# OpIoT_v_1_2.net
KiCad netlist of a schematic drawn in EAGLE
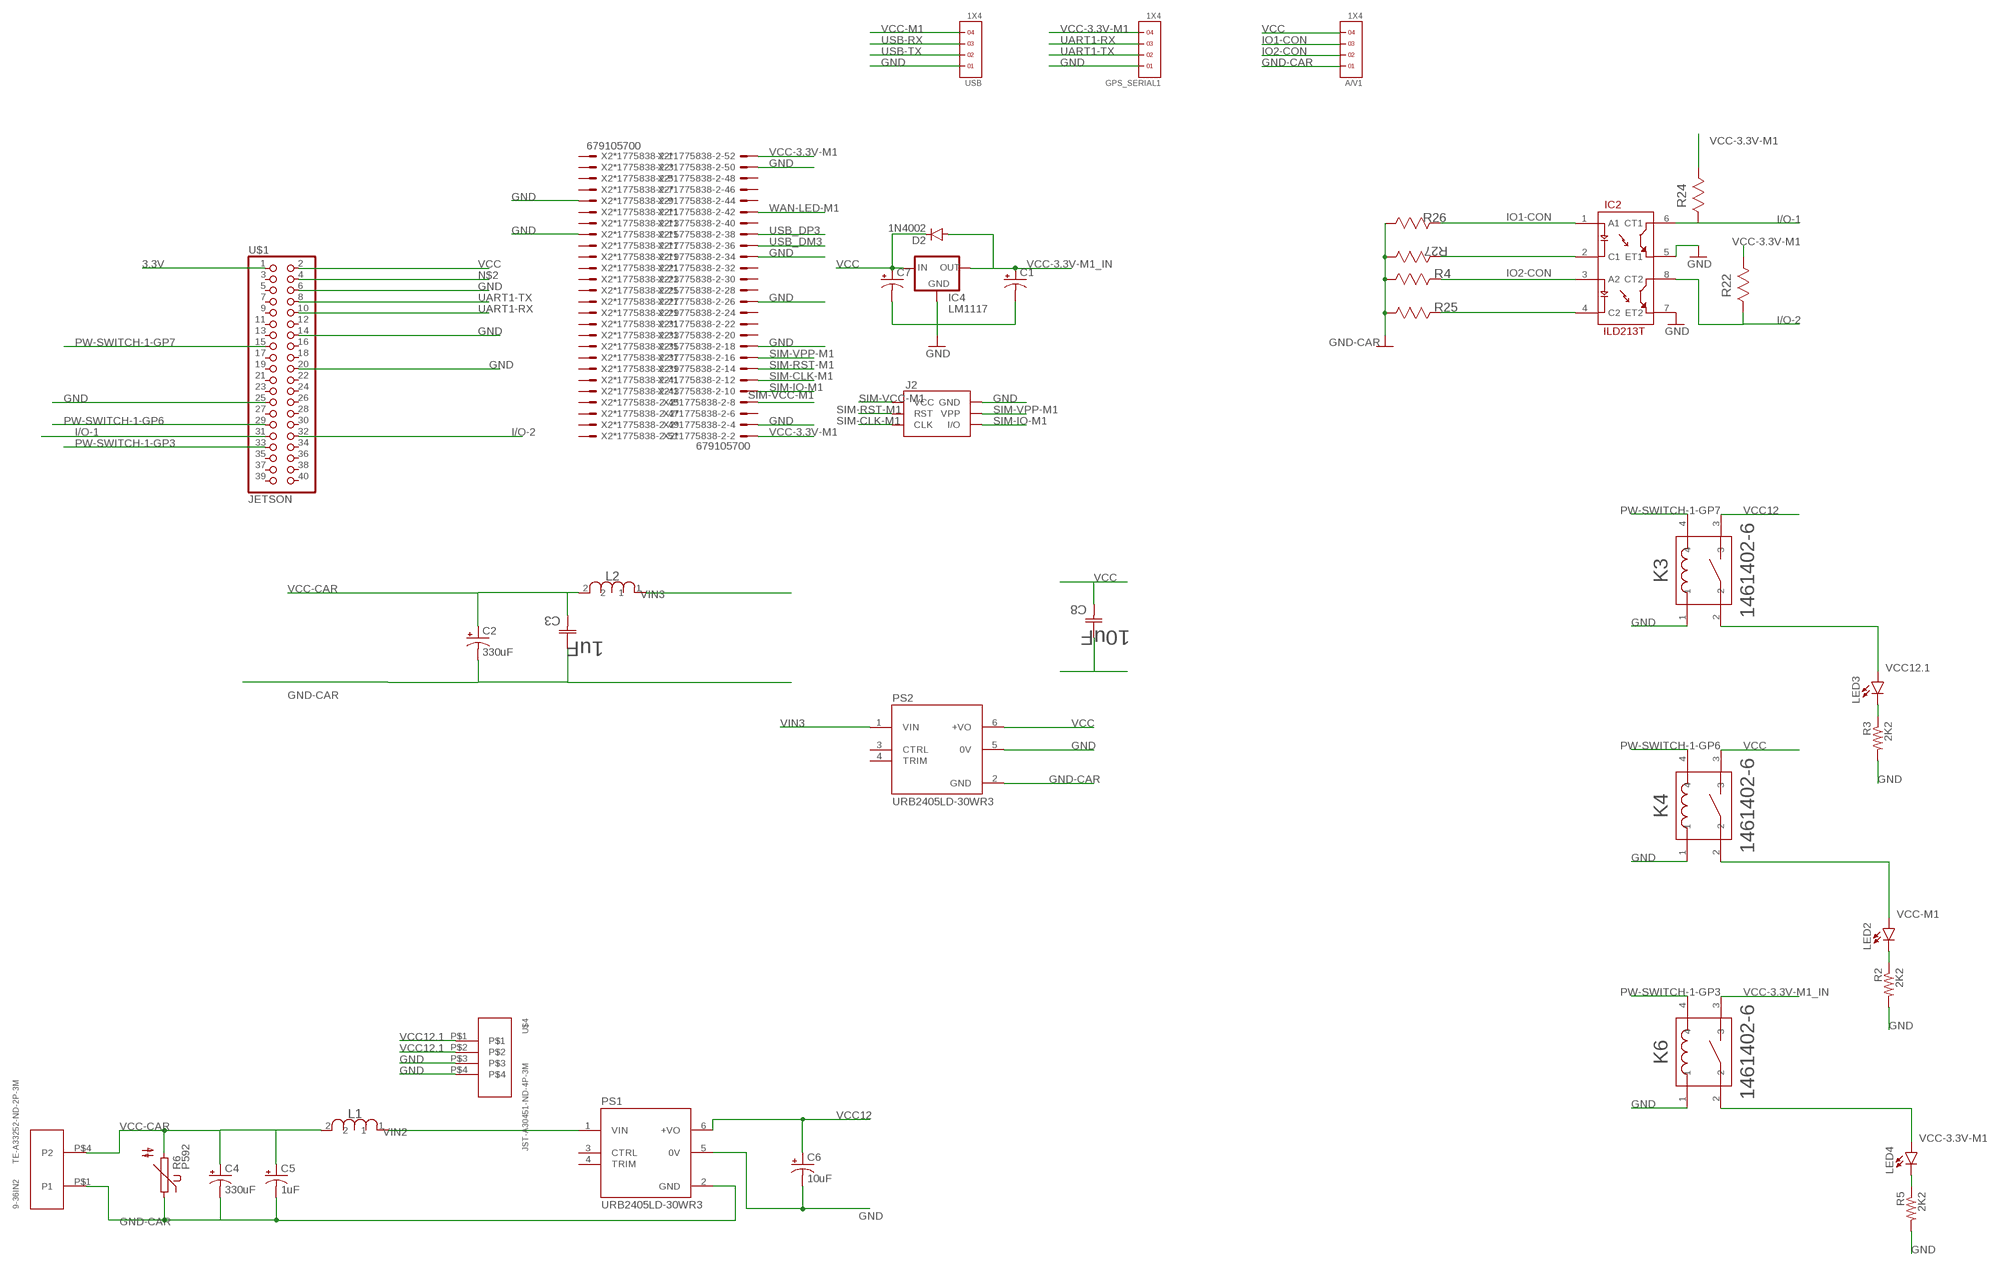
[diagram p0: schematic, sheet 1]

(export (version "E")
  (design (tool "Eeschema 10.0.6"))
  (components
    (comp (ref "9-36IN2")
      (value "TE-A33252-ND-2P-3M")
      (footprint "eagle-import:TE-A33252-ND-2P-3M")
      (libsource (lib "eagle-import") (part "TE-A33252-ND-2P-3M"))
    )
    (comp (ref "A/V1")
      (value "1X4")
      (footprint "eagle-import:1X4")
      (libsource (lib "eagle-import") (part "1X4"))
    )
    (comp (ref "C1")
      (value "CAP_POL1206-KIT")
      (footprint "eagle-import:EIA3216-KIT")
      (libsource (lib "eagle-import") (part "CAP_POL1206-KIT"))
    )
    (comp (ref "C2")
      (value "330uF")
      (footprint "eagle-import:UD-10X10_NICHICON")
      (libsource (lib "eagle-import") (part "CPOL-USUD-10X10"))
    )
    (comp (ref "C3")
      (value "1uF")
      (footprint "eagle-import:CAPC3216X110N")
      (fields (field (name "MPN") "C1206C105K5RACTU") (field (name "TOLERANCE") "±10%"))
      (libsource (lib "eagle-import") (part "C1206C105K5RACTU"))
    )
    (comp (ref "C4")
      (value "330uF")
      (footprint "eagle-import:UD-10X10_NICHICON")
      (libsource (lib "eagle-import") (part "CPOL-USUD-10X10"))
    )
    (comp (ref "C5")
      (value "1uF")
      (footprint "eagle-import:EIA3216-KIT")
      (libsource (lib "eagle-import") (part "CAP_POL1206-KIT"))
    )
    (comp (ref "C6")
      (value "10uF")
      (footprint "eagle-import:EIA3216-KIT")
      (libsource (lib "eagle-import") (part "CAP_POL1206-KIT"))
    )
    (comp (ref "C7")
      (value "CAP_POL1206-KIT")
      (footprint "eagle-import:EIA3216-KIT")
      (libsource (lib "eagle-import") (part "CAP_POL1206-KIT"))
    )
    (comp (ref "C8")
      (value "10uF")
      (footprint "eagle-import:CAPC3216X110N")
      (fields (field (name "MPN") "C1206C105K5RACTU") (field (name "TOLERANCE") "±10%"))
      (libsource (lib "eagle-import") (part "C1206C105K5RACTU"))
    )
    (comp (ref "D2")
      (value "1N4002")
      (footprint "eagle-import:SMA-DIODE-KIT")
      (libsource (lib "eagle-import") (part "DIODESMA-KIT"))
    )
    (comp (ref "GPS_SERIAL1")
      (value "1X4")
      (footprint "eagle-import:1X4")
      (libsource (lib "eagle-import") (part "1X4"))
    )
    (comp (ref "IC2")
      (value "ILD213T")
      (footprint "eagle-import:SO08")
      (libsource (lib "eagle-import") (part "ILD213T"))
    )
    (comp (ref "IC4")
      (value "LM1117")
      (footprint "eagle-import:SOT223")
      (fields (field (name "MF") "Texas Instruments") (field (name "MP") "LM1117MP-3.3/NOPB"))
      (libsource (lib "eagle-import") (part "LM1117"))
    )
    (comp (ref "J2")
      (value "SIMHOLDERSIM")
      (footprint "eagle-import:SIMHOLDER")
      (libsource (lib "eagle-import") (part "SIMHOLDERSIM"))
    )
    (comp (ref "K3")
      (value "1461402-6")
      (footprint "eagle-import:RELAY_1461402-6")
      (fields (field (name "MF") "TE Connectivity") (field (name "MP") "OJE-SH-112HM,000"))
      (libsource (lib "eagle-import") (part "1461402-6"))
    )
    (comp (ref "K4")
      (value "1461402-6")
      (footprint "eagle-import:RELAY_1461402-6")
      (fields (field (name "MF") "TE Connectivity") (field (name "MP") "OJE-SH-112HM,000"))
      (libsource (lib "eagle-import") (part "1461402-6"))
    )
    (comp (ref "K6")
      (value "1461402-6")
      (footprint "eagle-import:RELAY_1461402-6")
      (fields (field (name "MF") "TE Connectivity") (field (name "MP") "OJE-SH-112HM,000"))
      (libsource (lib "eagle-import") (part "1461402-6"))
    )
    (comp (ref "L1")
      (value "4.7uH")
      (footprint "eagle-import:INDC3225X22N")
      (fields (field (name "MPN") "PM1210-1R0J-RC") (field (name "TOLERANCE") "±5 %"))
      (libsource (lib "eagle-import") (part "PM1210-1R0J-RC"))
    )
    (comp (ref "L2")
      (value "4.7uH")
      (footprint "eagle-import:INDC3225X22N")
      (fields (field (name "MPN") "PM1210-1R0J-RC") (field (name "TOLERANCE") "±5 %"))
      (libsource (lib "eagle-import") (part "PM1210-1R0J-RC"))
    )
    (comp (ref "LED2")
      (value "LEDCHIPLED_1206")
      (footprint "eagle-import:CHIPLED_1206")
      (libsource (lib "eagle-import") (part "LEDCHIPLED_1206"))
    )
    (comp (ref "LED3")
      (value "LEDCHIPLED_1206")
      (footprint "eagle-import:CHIPLED_1206")
      (libsource (lib "eagle-import") (part "LEDCHIPLED_1206"))
    )
    (comp (ref "LED4")
      (value "LEDCHIPLED_1206")
      (footprint "eagle-import:CHIPLED_1206")
      (libsource (lib "eagle-import") (part "LEDCHIPLED_1206"))
    )
    (comp (ref "PS1")
      (value "URB2405LD-30WR3")
      (footprint "eagle-import:CONV_URB2405LD-30WR3")
      (fields (field (name "MF") "MORNSUN"))
      (libsource (lib "eagle-import") (part "URB2405LD-30WR3"))
    )
    (comp (ref "PS2")
      (value "URB2405LD-30WR3")
      (footprint "eagle-import:CONV_URB2405LD-30WR3")
      (fields (field (name "MF") "MORNSUN"))
      (libsource (lib "eagle-import") (part "URB2405LD-30WR3"))
    )
    (comp (ref "R2")
      (value "2K2")
      (footprint "eagle-import:M1206")
      (libsource (lib "eagle-import") (part "R-US_M1206"))
    )
    (comp (ref "R3")
      (value "2K2")
      (footprint "eagle-import:M1206")
      (libsource (lib "eagle-import") (part "R-US_M1206"))
    )
    (comp (ref "R4")
      (value "4K7")
      (footprint "eagle-import:RESC3216X71N")
      (fields (field (name "MPN") "ERJ-8ENF1501V") (field (name "TOLERANCE") "±1 %"))
      (libsource (lib "eagle-import") (part "ERJ-8ENF1501V"))
    )
    (comp (ref "R5")
      (value "2K2")
      (footprint "eagle-import:M1206")
      (libsource (lib "eagle-import") (part "R-US_M1206"))
    )
    (comp (ref "R6")
      (value "P592")
      (footprint "eagle-import:P592")
      (libsource (lib "eagle-import") (part "P592"))
    )
    (comp (ref "R22")
      (value "300K")
      (footprint "eagle-import:RESC3216X71N")
      (fields (field (name "MPN") "ERJ-8ENF1501V") (field (name "TOLERANCE") "±1 %"))
      (libsource (lib "eagle-import") (part "ERJ-8ENF1501V"))
    )
    (comp (ref "R24")
      (value "300K")
      (footprint "eagle-import:RESC3216X71N")
      (fields (field (name "MPN") "ERJ-8ENF1501V") (field (name "TOLERANCE") "±1 %"))
      (libsource (lib "eagle-import") (part "ERJ-8ENF1501V"))
    )
    (comp (ref "R25")
      (value "2.2K")
      (footprint "eagle-import:RESC3216X71N")
      (fields (field (name "MPN") "ERJ-8ENF1501V") (field (name "TOLERANCE") "±1 %"))
      (libsource (lib "eagle-import") (part "ERJ-8ENF1501V"))
    )
    (comp (ref "R26")
      (value "4K7")
      (footprint "eagle-import:RESC3216X71N")
      (fields (field (name "MPN") "ERJ-8ENF1501V") (field (name "TOLERANCE") "±1 %"))
      (libsource (lib "eagle-import") (part "ERJ-8ENF1501V"))
    )
    (comp (ref "R27")
      (value "2.2K")
      (footprint "eagle-import:RESC3216X71N")
      (fields (field (name "MPN") "ERJ-8ENF1501V") (field (name "TOLERANCE") "±1 %"))
      (libsource (lib "eagle-import") (part "ERJ-8ENF1501V"))
    )
    (comp (ref "U$1")
      (value "JETSON")
      (footprint "eagle-import:2X20")
      (libsource (lib "eagle-import") (part "JETSON"))
    )
    (comp (ref "U$4")
      (value "JST-A30451-ND-4P-3M")
      (footprint "eagle-import:TE-A30451-4P-TH-3M")
      (libsource (lib "eagle-import") (part "JST-A30451-ND-4P-3M"))
    )
    (comp (ref "USB")
      (value "1X4")
      (footprint "eagle-import:1X4")
      (libsource (lib "eagle-import") (part "1X4"))
    )
    (comp (ref "X2*1775838-2")
      (value "679105700")
      (footprint "eagle-import:679105700")
      (fields (field (name "MF") "MOLEX") (field (name "MPN") "67910-5700"))
      (libsource (lib "eagle-import") (part "679105700"))
    )
  )
  (nets
    (net (code "1") (name "/3.3V") (class "Default")
      (node (ref "U$1") (pin "1") (pinfunction "1_1") (pintype "passive"))
    )
    (net (code "2") (name "/IO1-CON") (class "Default")
      (node (ref "A/V1") (pin "3") (pinfunction "3_3") (pintype "bidirectional"))
      (node (ref "IC2") (pin "1") (pinfunction "A1_1") (pintype "bidirectional"))
      (node (ref "R26") (pin "1") (pinfunction "R1_1") (pintype "passive"))
    )
    (net (code "3") (name "/IO2-CON") (class "Default")
      (node (ref "A/V1") (pin "2") (pinfunction "2_2") (pintype "bidirectional"))
      (node (ref "IC2") (pin "3") (pinfunction "A2_3") (pintype "bidirectional"))
      (node (ref "R4") (pin "1") (pinfunction "R1_1") (pintype "passive"))
    )
    (net (code "4") (name "/I{slash}O-1") (class "Default")
      (node (ref "IC2") (pin "6") (pinfunction "CT1_6") (pintype "bidirectional"))
      (node (ref "R24") (pin "2") (pinfunction "R2_2") (pintype "passive"))
      (node (ref "U$1") (pin "31") (pinfunction "31_31") (pintype "passive"))
    )
    (net (code "5") (name "/I{slash}O-2") (class "Default")
      (node (ref "IC2") (pin "8") (pinfunction "CT2_8") (pintype "bidirectional"))
      (node (ref "R22") (pin "2") (pinfunction "R2_2") (pintype "passive"))
      (node (ref "U$1") (pin "32") (pinfunction "32_32") (pintype "passive"))
    )
    (net (code "6") (name "/N$2") (class "Default")
      (node (ref "U$1") (pin "4") (pinfunction "4_4") (pintype "passive"))
    )
    (net (code "7") (name "/PW-SWITCH-1-GP3") (class "Default")
      (node (ref "K6") (pin "4") (pinfunction "4_4") (pintype "passive"))
      (node (ref "U$1") (pin "33") (pinfunction "33_33") (pintype "passive"))
    )
    (net (code "8") (name "/PW-SWITCH-1-GP6") (class "Default")
      (node (ref "K4") (pin "4") (pinfunction "4_4") (pintype "passive"))
      (node (ref "U$1") (pin "29") (pinfunction "29_29") (pintype "passive"))
    )
    (net (code "9") (name "/PW-SWITCH-1-GP7") (class "Default")
      (node (ref "K3") (pin "4") (pinfunction "4_4") (pintype "passive"))
      (node (ref "U$1") (pin "15") (pinfunction "15_15") (pintype "passive"))
    )
    (net (code "10") (name "/SIM-CLK-M1") (class "Default")
      (node (ref "J2") (pin "C3") (pinfunction "CLK_C3") (pintype "input"))
      (node (ref "X2*1775838-2") (pin "12") (pinfunction "S_12") (pintype "passive"))
    )
    (net (code "11") (name "/SIM-IO-M1") (class "Default")
      (node (ref "J2") (pin "C7") (pinfunction "I/O_C7") (pintype "bidirectional"))
      (node (ref "X2*1775838-2") (pin "10") (pinfunction "S_10") (pintype "passive"))
    )
    (net (code "12") (name "/SIM-RST-M1") (class "Default")
      (node (ref "J2") (pin "C2") (pinfunction "RST_C2") (pintype "input"))
      (node (ref "X2*1775838-2") (pin "14") (pinfunction "S_14") (pintype "passive"))
    )
    (net (code "13") (name "/SIM-VCC-M1") (class "Default")
      (node (ref "J2") (pin "C1") (pinfunction "VCC_C1") (pintype "power_in"))
      (node (ref "X2*1775838-2") (pin "8") (pinfunction "S_8") (pintype "passive"))
    )
    (net (code "14") (name "/SIM-VPP-M1") (class "Default")
      (node (ref "J2") (pin "C6") (pinfunction "VPP_C6") (pintype "input"))
      (node (ref "X2*1775838-2") (pin "16") (pinfunction "S_16") (pintype "passive"))
    )
    (net (code "15") (name "/UART1-RX") (class "Default")
      (node (ref "GPS_SERIAL1") (pin "3") (pinfunction "3_3") (pintype "bidirectional"))
      (node (ref "U$1") (pin "10") (pinfunction "10_10") (pintype "passive"))
    )
    (net (code "16") (name "/UART1-TX") (class "Default")
      (node (ref "GPS_SERIAL1") (pin "2") (pinfunction "2_2") (pintype "bidirectional"))
      (node (ref "U$1") (pin "8") (pinfunction "8_8") (pintype "passive"))
    )
    (net (code "17") (name "/USB-RX") (class "Default")
      (node (ref "USB") (pin "3") (pinfunction "3_3") (pintype "bidirectional"))
    )
    (net (code "18") (name "/USB-TX") (class "Default")
      (node (ref "USB") (pin "2") (pinfunction "2_2") (pintype "bidirectional"))
    )
    (net (code "19") (name "/USB_DM3") (class "Default")
      (node (ref "X2*1775838-2") (pin "36") (pinfunction "S_36") (pintype "passive"))
    )
    (net (code "20") (name "/USB_DP3") (class "Default")
      (node (ref "X2*1775838-2") (pin "38") (pinfunction "S_38") (pintype "passive"))
    )
    (net (code "21") (name "/VCC") (class "Default")
      (node (ref "A/V1") (pin "4") (pinfunction "4_4") (pintype "bidirectional"))
      (node (ref "C7") (pin "A") (pinfunction "+_A") (pintype "passive"))
      (node (ref "C8") (pin "2") (pinfunction "C2_2") (pintype "passive"))
      (node (ref "D2") (pin "C") (pinfunction "C_C") (pintype "passive"))
      (node (ref "IC4") (pin "3") (pinfunction "IN_3") (pintype "input"))
      (node (ref "K4") (pin "3") (pinfunction "3_3") (pintype "passive"))
      (node (ref "PS2") (pin "6") (pinfunction "+VO_6") (pintype "output"))
      (node (ref "U$1") (pin "2") (pinfunction "2_2") (pintype "passive"))
    )
    (net (code "22") (name "/VCC-3.3V-M1") (class "Default")
      (node (ref "GPS_SERIAL1") (pin "4") (pinfunction "4_4") (pintype "bidirectional"))
      (node (ref "K6") (pin "2") (pinfunction "2_2") (pintype "passive"))
      (node (ref "LED4") (pin "A") (pinfunction "A_A") (pintype "passive"))
      (node (ref "R22") (pin "1") (pinfunction "R1_1") (pintype "passive"))
      (node (ref "R24") (pin "1") (pinfunction "R1_1") (pintype "passive"))
      (node (ref "X2*1775838-2") (pin "2") (pinfunction "S_2") (pintype "passive"))
      (node (ref "X2*1775838-2") (pin "52") (pinfunction "S_52") (pintype "passive"))
    )
    (net (code "23") (name "/VCC-3.3V-M1_IN") (class "Default")
      (node (ref "C1") (pin "A") (pinfunction "+_A") (pintype "passive"))
      (node (ref "D2") (pin "A") (pinfunction "A_A") (pintype "passive"))
      (node (ref "IC4") (pin "2") (pinfunction "OUT_2") (pintype "passive"))
      (node (ref "K6") (pin "3") (pinfunction "3_3") (pintype "passive"))
    )
    (net (code "24") (name "/VCC-CAR") (class "Default")
      (node (ref "9-36IN2") (pin "P$4") (pinfunction "P2_P$4") (pintype "bidirectional"))
      (node (ref "C2") (pin "+") (pinfunction "+_+") (pintype "passive"))
      (node (ref "C3") (pin "2") (pinfunction "C2_2") (pintype "passive"))
      (node (ref "C4") (pin "+") (pinfunction "+_+") (pintype "passive"))
      (node (ref "C5") (pin "A") (pinfunction "+_A") (pintype "passive"))
      (node (ref "L1") (pin "2") (pinfunction "2_2") (pintype "passive"))
      (node (ref "L2") (pin "2") (pinfunction "2_2") (pintype "passive"))
      (node (ref "R6") (pin "2") (pinfunction "2_2") (pintype "passive"))
    )
    (net (code "25") (name "/VCC-M1") (class "Default")
      (node (ref "K4") (pin "2") (pinfunction "2_2") (pintype "passive"))
      (node (ref "LED2") (pin "A") (pinfunction "A_A") (pintype "passive"))
      (node (ref "USB") (pin "4") (pinfunction "4_4") (pintype "bidirectional"))
    )
    (net (code "26") (name "/VCC12") (class "Default")
      (node (ref "C6") (pin "A") (pinfunction "+_A") (pintype "passive"))
      (node (ref "K3") (pin "3") (pinfunction "3_3") (pintype "passive"))
      (node (ref "PS1") (pin "6") (pinfunction "+VO_6") (pintype "output"))
    )
    (net (code "27") (name "/VCC12.1") (class "Default")
      (node (ref "K3") (pin "2") (pinfunction "2_2") (pintype "passive"))
      (node (ref "LED3") (pin "A") (pinfunction "A_A") (pintype "passive"))
      (node (ref "U$4") (pin "P$1") (pinfunction "P$1_P$1") (pintype "bidirectional"))
      (node (ref "U$4") (pin "P$2") (pinfunction "P$2_P$2") (pintype "bidirectional"))
    )
    (net (code "28") (name "/VIN2") (class "Default")
      (node (ref "L1") (pin "1") (pinfunction "1_1") (pintype "passive"))
      (node (ref "PS1") (pin "1") (pinfunction "VIN_1") (pintype "input"))
    )
    (net (code "29") (name "/VIN3") (class "Default")
      (node (ref "L2") (pin "1") (pinfunction "1_1") (pintype "passive"))
      (node (ref "PS2") (pin "1") (pinfunction "VIN_1") (pintype "input"))
    )
    (net (code "30") (name "/WAN-LED-M1") (class "Default")
      (node (ref "X2*1775838-2") (pin "42") (pinfunction "S_42") (pintype "passive"))
    )
    (net (code "31") (name "GND") (class "Default")
      (node (ref "C1") (pin "C") (pinfunction "-_C") (pintype "passive"))
      (node (ref "C6") (pin "C") (pinfunction "-_C") (pintype "passive"))
      (node (ref "C7") (pin "C") (pinfunction "-_C") (pintype "passive"))
      (node (ref "C8") (pin "1") (pinfunction "C1_1") (pintype "passive"))
      (node (ref "GPS_SERIAL1") (pin "1") (pinfunction "1_1") (pintype "bidirectional"))
      (node (ref "IC2") (pin "5") (pinfunction "ET1_5") (pintype "bidirectional"))
      (node (ref "IC2") (pin "7") (pinfunction "ET2_7") (pintype "bidirectional"))
      (node (ref "IC4") (pin "1") (pinfunction "GND_1") (pintype "input"))
      (node (ref "J2") (pin "C5") (pinfunction "GND_C5") (pintype "power_in"))
      (node (ref "K3") (pin "1") (pinfunction "1_1") (pintype "passive"))
      (node (ref "K4") (pin "1") (pinfunction "1_1") (pintype "passive"))
      (node (ref "K6") (pin "1") (pinfunction "1_1") (pintype "passive"))
      (node (ref "PS1") (pin "5") (pinfunction "0V_5") (pintype "output"))
      (node (ref "PS2") (pin "5") (pinfunction "0V_5") (pintype "output"))
      (node (ref "R2") (pin "2") (pinfunction "2_2") (pintype "passive"))
      (node (ref "R3") (pin "2") (pinfunction "2_2") (pintype "passive"))
      (node (ref "R5") (pin "2") (pinfunction "2_2") (pintype "passive"))
      (node (ref "U$1") (pin "14") (pinfunction "14_14") (pintype "passive"))
      (node (ref "U$1") (pin "20") (pinfunction "20_20") (pintype "passive"))
      (node (ref "U$1") (pin "25") (pinfunction "25_25") (pintype "passive"))
      (node (ref "U$1") (pin "6") (pinfunction "6_6") (pintype "passive"))
      (node (ref "U$4") (pin "P$3") (pinfunction "P$3_P$3") (pintype "bidirectional"))
      (node (ref "U$4") (pin "P$4") (pinfunction "P$4_P$4") (pintype "bidirectional"))
      (node (ref "USB") (pin "1") (pinfunction "1_1") (pintype "bidirectional"))
      (node (ref "X2*1775838-2") (pin "15") (pinfunction "S_15") (pintype "passive"))
      (node (ref "X2*1775838-2") (pin "18") (pinfunction "S_18") (pintype "passive"))
      (node (ref "X2*1775838-2") (pin "26") (pinfunction "S_26") (pintype "passive"))
      (node (ref "X2*1775838-2") (pin "34") (pinfunction "S_34") (pintype "passive"))
      (node (ref "X2*1775838-2") (pin "4") (pinfunction "S_4") (pintype "passive"))
      (node (ref "X2*1775838-2") (pin "50") (pinfunction "S_50") (pintype "passive"))
      (node (ref "X2*1775838-2") (pin "9") (pinfunction "S_9") (pintype "passive"))
    )
    (net (code "32") (name "GND-CAR") (class "Default")
      (node (ref "9-36IN2") (pin "P$1") (pinfunction "P1_P$1") (pintype "bidirectional"))
      (node (ref "A/V1") (pin "1") (pinfunction "1_1") (pintype "bidirectional"))
      (node (ref "C2") (pin "-") (pinfunction "-_-") (pintype "passive"))
      (node (ref "C3") (pin "1") (pinfunction "C1_1") (pintype "passive"))
      (node (ref "C4") (pin "-") (pinfunction "-_-") (pintype "passive"))
      (node (ref "C5") (pin "C") (pinfunction "-_C") (pintype "passive"))
      (node (ref "PS1") (pin "2") (pinfunction "GND_2") (pintype "power_in"))
      (node (ref "PS2") (pin "2") (pinfunction "GND_2") (pintype "power_in"))
      (node (ref "R25") (pin "1") (pinfunction "R1_1") (pintype "passive"))
      (node (ref "R26") (pin "2") (pinfunction "R2_2") (pintype "passive"))
      (node (ref "R27") (pin "1") (pinfunction "R1_1") (pintype "passive"))
      (node (ref "R4") (pin "2") (pinfunction "R2_2") (pintype "passive"))
      (node (ref "R6") (pin "1") (pinfunction "1_1") (pintype "passive"))
    )
    (net (code "33") (name "Net-(IC2-C1)") (class "Default")
      (node (ref "IC2") (pin "2") (pinfunction "C1_2") (pintype "bidirectional"))
      (node (ref "R27") (pin "2") (pinfunction "R2_2") (pintype "passive"))
    )
    (net (code "34") (name "Net-(IC2-C2)") (class "Default")
      (node (ref "IC2") (pin "4") (pinfunction "C2_4") (pintype "bidirectional"))
      (node (ref "R25") (pin "2") (pinfunction "R2_2") (pintype "passive"))
    )
    (net (code "35") (name "Net-(LED2-PadC)") (class "Default")
      (node (ref "LED2") (pin "C") (pinfunction "C_C") (pintype "passive"))
      (node (ref "R2") (pin "1") (pinfunction "1_1") (pintype "passive"))
    )
    (net (code "36") (name "Net-(LED3-PadC)") (class "Default")
      (node (ref "LED3") (pin "C") (pinfunction "C_C") (pintype "passive"))
      (node (ref "R3") (pin "1") (pinfunction "1_1") (pintype "passive"))
    )
    (net (code "37") (name "Net-(LED4-PadC)") (class "Default")
      (node (ref "LED4") (pin "C") (pinfunction "C_C") (pintype "passive"))
      (node (ref "R5") (pin "1") (pinfunction "1_1") (pintype "passive"))
    )
    (net (code "38") (name "unconnected-(PS1-CTRL-Pad3)") (class "Default")
      (node (ref "PS1") (pin "3") (pinfunction "CTRL_3") (pintype "input"))
    )
    (net (code "39") (name "unconnected-(PS1-TRIM-Pad4)") (class "Default")
      (node (ref "PS1") (pin "4") (pinfunction "TRIM_4") (pintype "input"))
    )
    (net (code "40") (name "unconnected-(PS2-CTRL-Pad3)") (class "Default")
      (node (ref "PS2") (pin "3") (pinfunction "CTRL_3") (pintype "input"))
    )
    (net (code "41") (name "unconnected-(PS2-TRIM-Pad4)") (class "Default")
      (node (ref "PS2") (pin "4") (pinfunction "TRIM_4") (pintype "input"))
    )
    (net (code "42") (name "unconnected-(U$1-Pad3)") (class "Default")
      (node (ref "U$1") (pin "3") (pinfunction "3_3") (pintype "passive"))
    )
    (net (code "43") (name "unconnected-(U$1-Pad5)") (class "Default")
      (node (ref "U$1") (pin "5") (pinfunction "5_5") (pintype "passive"))
    )
    (net (code "44") (name "unconnected-(U$1-Pad7)") (class "Default")
      (node (ref "U$1") (pin "7") (pinfunction "7_7") (pintype "passive"))
    )
    (net (code "45") (name "unconnected-(U$1-Pad9)") (class "Default")
      (node (ref "U$1") (pin "9") (pinfunction "9_9") (pintype "passive"))
    )
    (net (code "46") (name "unconnected-(U$1-Pad11)") (class "Default")
      (node (ref "U$1") (pin "11") (pinfunction "11_11") (pintype "passive"))
    )
    (net (code "47") (name "unconnected-(U$1-Pad12)") (class "Default")
      (node (ref "U$1") (pin "12") (pinfunction "12_12") (pintype "passive"))
    )
    (net (code "48") (name "unconnected-(U$1-Pad13)") (class "Default")
      (node (ref "U$1") (pin "13") (pinfunction "13_13") (pintype "passive"))
    )
    (net (code "49") (name "unconnected-(U$1-Pad16)") (class "Default")
      (node (ref "U$1") (pin "16") (pinfunction "16_16") (pintype "passive"))
    )
    (net (code "50") (name "unconnected-(U$1-Pad17)") (class "Default")
      (node (ref "U$1") (pin "17") (pinfunction "17_17") (pintype "passive"))
    )
    (net (code "51") (name "unconnected-(U$1-Pad18)") (class "Default")
      (node (ref "U$1") (pin "18") (pinfunction "18_18") (pintype "passive"))
    )
    (net (code "52") (name "unconnected-(U$1-Pad19)") (class "Default")
      (node (ref "U$1") (pin "19") (pinfunction "19_19") (pintype "passive"))
    )
    (net (code "53") (name "unconnected-(U$1-Pad21)") (class "Default")
      (node (ref "U$1") (pin "21") (pinfunction "21_21") (pintype "passive"))
    )
    (net (code "54") (name "unconnected-(U$1-Pad22)") (class "Default")
      (node (ref "U$1") (pin "22") (pinfunction "22_22") (pintype "passive"))
    )
    (net (code "55") (name "unconnected-(U$1-Pad23)") (class "Default")
      (node (ref "U$1") (pin "23") (pinfunction "23_23") (pintype "passive"))
    )
    (net (code "56") (name "unconnected-(U$1-Pad24)") (class "Default")
      (node (ref "U$1") (pin "24") (pinfunction "24_24") (pintype "passive"))
    )
    (net (code "57") (name "unconnected-(U$1-Pad26)") (class "Default")
      (node (ref "U$1") (pin "26") (pinfunction "26_26") (pintype "passive"))
    )
    (net (code "58") (name "unconnected-(U$1-Pad27)") (class "Default")
      (node (ref "U$1") (pin "27") (pinfunction "27_27") (pintype "passive"))
    )
    (net (code "59") (name "unconnected-(U$1-Pad28)") (class "Default")
      (node (ref "U$1") (pin "28") (pinfunction "28_28") (pintype "passive"))
    )
    (net (code "60") (name "unconnected-(U$1-Pad30)") (class "Default")
      (node (ref "U$1") (pin "30") (pinfunction "30_30") (pintype "passive"))
    )
    (net (code "61") (name "unconnected-(U$1-Pad34)") (class "Default")
      (node (ref "U$1") (pin "34") (pinfunction "34_34") (pintype "passive"))
    )
    (net (code "62") (name "unconnected-(U$1-Pad35)") (class "Default")
      (node (ref "U$1") (pin "35") (pinfunction "35_35") (pintype "passive"))
    )
    (net (code "63") (name "unconnected-(U$1-Pad36)") (class "Default")
      (node (ref "U$1") (pin "36") (pinfunction "36_36") (pintype "passive"))
    )
    (net (code "64") (name "unconnected-(U$1-Pad37)") (class "Default")
      (node (ref "U$1") (pin "37") (pinfunction "37_37") (pintype "passive"))
    )
    (net (code "65") (name "unconnected-(U$1-Pad38)") (class "Default")
      (node (ref "U$1") (pin "38") (pinfunction "38_38") (pintype "passive"))
    )
    (net (code "66") (name "unconnected-(U$1-Pad39)") (class "Default")
      (node (ref "U$1") (pin "39") (pinfunction "39_39") (pintype "passive"))
    )
    (net (code "67") (name "unconnected-(U$1-Pad40)") (class "Default")
      (node (ref "U$1") (pin "40") (pinfunction "40_40") (pintype "passive"))
    )
    (net (code "68") (name "unconnected-(X2*1775838-2A-S-Pad1)") (class "Default")
      (node (ref "X2*1775838-2") (pin "1") (pinfunction "S_1") (pintype "passive"))
    )
    (net (code "69") (name "unconnected-(X2*1775838-2AA-S-Pad33)") (class "Default")
      (node (ref "X2*1775838-2") (pin "33") (pinfunction "S_33") (pintype "passive"))
    )
    (net (code "70") (name "unconnected-(X2*1775838-2AC-S-Pad35)") (class "Default")
      (node (ref "X2*1775838-2") (pin "35") (pinfunction "S_35") (pintype "passive"))
    )
    (net (code "71") (name "unconnected-(X2*1775838-2AE-S-Pad37)") (class "Default")
      (node (ref "X2*1775838-2") (pin "37") (pinfunction "S_37") (pintype "passive"))
    )
    (net (code "72") (name "unconnected-(X2*1775838-2AG-S-Pad39)") (class "Default")
      (node (ref "X2*1775838-2") (pin "39") (pinfunction "S_39") (pintype "passive"))
    )
    (net (code "73") (name "unconnected-(X2*1775838-2AI-S-Pad40)") (class "Default")
      (node (ref "X2*1775838-2") (pin "40") (pinfunction "S_40") (pintype "passive"))
    )
    (net (code "74") (name "unconnected-(X2*1775838-2AJ-S-Pad41)") (class "Default")
      (node (ref "X2*1775838-2") (pin "41") (pinfunction "S_41") (pintype "passive"))
    )
    (net (code "75") (name "unconnected-(X2*1775838-2AL-S-Pad43)") (class "Default")
      (node (ref "X2*1775838-2") (pin "43") (pinfunction "S_43") (pintype "passive"))
    )
    (net (code "76") (name "unconnected-(X2*1775838-2AM-S-Pad44)") (class "Default")
      (node (ref "X2*1775838-2") (pin "44") (pinfunction "S_44") (pintype "passive"))
    )
    (net (code "77") (name "unconnected-(X2*1775838-2AN-S-Pad45)") (class "Default")
      (node (ref "X2*1775838-2") (pin "45") (pinfunction "S_45") (pintype "passive"))
    )
    (net (code "78") (name "unconnected-(X2*1775838-2AO-S-Pad46)") (class "Default")
      (node (ref "X2*1775838-2") (pin "46") (pinfunction "S_46") (pintype "passive"))
    )
    (net (code "79") (name "unconnected-(X2*1775838-2AP-S-Pad47)") (class "Default")
      (node (ref "X2*1775838-2") (pin "47") (pinfunction "S_47") (pintype "passive"))
    )
    (net (code "80") (name "unconnected-(X2*1775838-2AQ-S-Pad48)") (class "Default")
      (node (ref "X2*1775838-2") (pin "48") (pinfunction "S_48") (pintype "passive"))
    )
    (net (code "81") (name "unconnected-(X2*1775838-2AR-S-Pad49)") (class "Default")
      (node (ref "X2*1775838-2") (pin "49") (pinfunction "S_49") (pintype "passive"))
    )
    (net (code "82") (name "unconnected-(X2*1775838-2AS-S-Pad5)") (class "Default")
      (node (ref "X2*1775838-2") (pin "5") (pinfunction "S_5") (pintype "passive"))
    )
    (net (code "83") (name "unconnected-(X2*1775838-2AU-S-Pad51)") (class "Default")
      (node (ref "X2*1775838-2") (pin "51") (pinfunction "S_51") (pintype "passive"))
    )
    (net (code "84") (name "unconnected-(X2*1775838-2AW-S-Pad6)") (class "Default")
      (node (ref "X2*1775838-2") (pin "6") (pinfunction "S_6") (pintype "passive"))
    )
    (net (code "85") (name "unconnected-(X2*1775838-2AX-S-Pad7)") (class "Default")
      (node (ref "X2*1775838-2") (pin "7") (pinfunction "S_7") (pintype "passive"))
    )
    (net (code "86") (name "unconnected-(X2*1775838-2C-S-Pad11)") (class "Default")
      (node (ref "X2*1775838-2") (pin "11") (pinfunction "S_11") (pintype "passive"))
    )
    (net (code "87") (name "unconnected-(X2*1775838-2E-S-Pad13)") (class "Default")
      (node (ref "X2*1775838-2") (pin "13") (pinfunction "S_13") (pintype "passive"))
    )
    (net (code "88") (name "unconnected-(X2*1775838-2I-S-Pad17)") (class "Default")
      (node (ref "X2*1775838-2") (pin "17") (pinfunction "S_17") (pintype "passive"))
    )
    (net (code "89") (name "unconnected-(X2*1775838-2K-S-Pad19)") (class "Default")
      (node (ref "X2*1775838-2") (pin "19") (pinfunction "S_19") (pintype "passive"))
    )
    (net (code "90") (name "unconnected-(X2*1775838-2M-S-Pad20)") (class "Default")
      (node (ref "X2*1775838-2") (pin "20") (pinfunction "S_20") (pintype "passive"))
    )
    (net (code "91") (name "unconnected-(X2*1775838-2N-S-Pad21)") (class "Default")
      (node (ref "X2*1775838-2") (pin "21") (pinfunction "S_21") (pintype "passive"))
    )
    (net (code "92") (name "unconnected-(X2*1775838-2O-S-Pad22)") (class "Default")
      (node (ref "X2*1775838-2") (pin "22") (pinfunction "S_22") (pintype "passive"))
    )
    (net (code "93") (name "unconnected-(X2*1775838-2P-S-Pad23)") (class "Default")
      (node (ref "X2*1775838-2") (pin "23") (pinfunction "S_23") (pintype "passive"))
    )
    (net (code "94") (name "unconnected-(X2*1775838-2Q-S-Pad24)") (class "Default")
      (node (ref "X2*1775838-2") (pin "24") (pinfunction "S_24") (pintype "passive"))
    )
    (net (code "95") (name "unconnected-(X2*1775838-2R-S-Pad25)") (class "Default")
      (node (ref "X2*1775838-2") (pin "25") (pinfunction "S_25") (pintype "passive"))
    )
    (net (code "96") (name "unconnected-(X2*1775838-2T-S-Pad27)") (class "Default")
      (node (ref "X2*1775838-2") (pin "27") (pinfunction "S_27") (pintype "passive"))
    )
    (net (code "97") (name "unconnected-(X2*1775838-2U-S-Pad28)") (class "Default")
      (node (ref "X2*1775838-2") (pin "28") (pinfunction "S_28") (pintype "passive"))
    )
    (net (code "98") (name "unconnected-(X2*1775838-2V-S-Pad29)") (class "Default")
      (node (ref "X2*1775838-2") (pin "29") (pinfunction "S_29") (pintype "passive"))
    )
    (net (code "99") (name "unconnected-(X2*1775838-2W-S-Pad3)") (class "Default")
      (node (ref "X2*1775838-2") (pin "3") (pinfunction "S_3") (pintype "passive"))
    )
    (net (code "100") (name "unconnected-(X2*1775838-2X-S-Pad30)") (class "Default")
      (node (ref "X2*1775838-2") (pin "30") (pinfunction "S_30") (pintype "passive"))
    )
    (net (code "101") (name "unconnected-(X2*1775838-2Y-S-Pad31)") (class "Default")
      (node (ref "X2*1775838-2") (pin "31") (pinfunction "S_31") (pintype "passive"))
    )
    (net (code "102") (name "unconnected-(X2*1775838-2Z-S-Pad32)") (class "Default")
      (node (ref "X2*1775838-2") (pin "32") (pinfunction "S_32") (pintype "passive"))
    )
  )
)
